# Connectors.net
KiCad netlist of a schematic drawn in Altium Designer
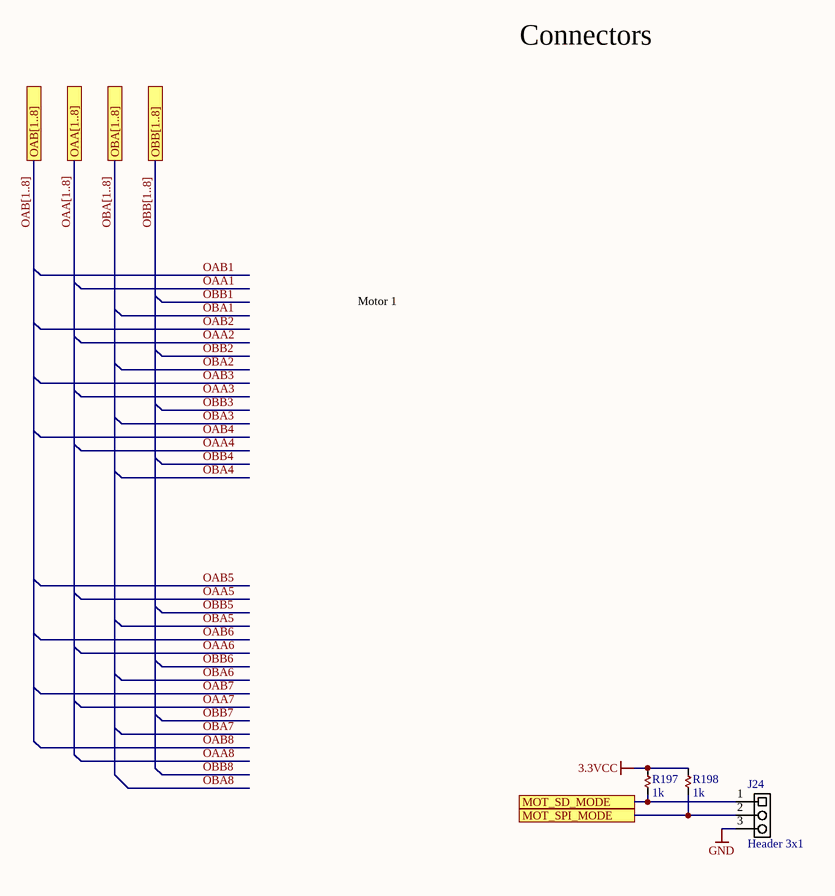
[diagram p0: Connectors.SchDoc]

(export (version "E")
  (design (tool "Eeschema 10.0.6"))
  (components
    (comp (ref "J24")
      (value "Header 3x1")
      (footprint "HDR3X1")
      (description "Header 3Pin 1Row T-Hole")
      (fields (field (name "MANUFACTURER") "Multicomp") (field (name "PART") "CONN 3Pin 1Row 0.1\""))
      (libsource (lib "Connectors") (part "Header 3x1 Male Pin"))
    )
    (comp (ref "R197")
      (value "1k")
      (footprint "R0402")
      (description "RES 0402 1k 63mW 1%")
      (fields (field (name "MANUFACTURER") "Yageo") (field (name "PART") "1k 1% 0402"))
      (libsource (lib "Resistors") (part "1k 1% 0402"))
    )
    (comp (ref "R198")
      (value "1k")
      (footprint "R0402")
      (description "RES 0402 1k 63mW 1%")
      (fields (field (name "MANUFACTURER") "Yageo") (field (name "PART") "1k 1% 0402"))
      (libsource (lib "Resistors") (part "1k 1% 0402"))
    )
  )
  (nets
    (net (code "1") (name "/MOT_SD_MODE") (class "Default")
      (node (ref "J24") (pin "1") (pinfunction "1_1") (pintype "passive"))
      (node (ref "R197") (pin "1") (pinfunction "1_1") (pintype "passive"))
    )
    (net (code "2") (name "/MOT_SPI_MODE") (class "Default")
      (node (ref "J24") (pin "2") (pinfunction "2_2") (pintype "passive"))
      (node (ref "R198") (pin "1") (pinfunction "1_1") (pintype "passive"))
    )
    (net (code "39") (name "3.3VCC") (class "Default")
      (node (ref "R197") (pin "2") (pinfunction "2_2") (pintype "passive"))
      (node (ref "R198") (pin "2") (pinfunction "2_2") (pintype "passive"))
    )
    (net (code "40") (name "GND") (class "Default")
      (node (ref "J24") (pin "3") (pinfunction "3_3") (pintype "passive"))
    )
  )
)
